# SCH_12-volt-power-EasyEDA.net
KiCad netlist of a schematic drawn in EasyEDA
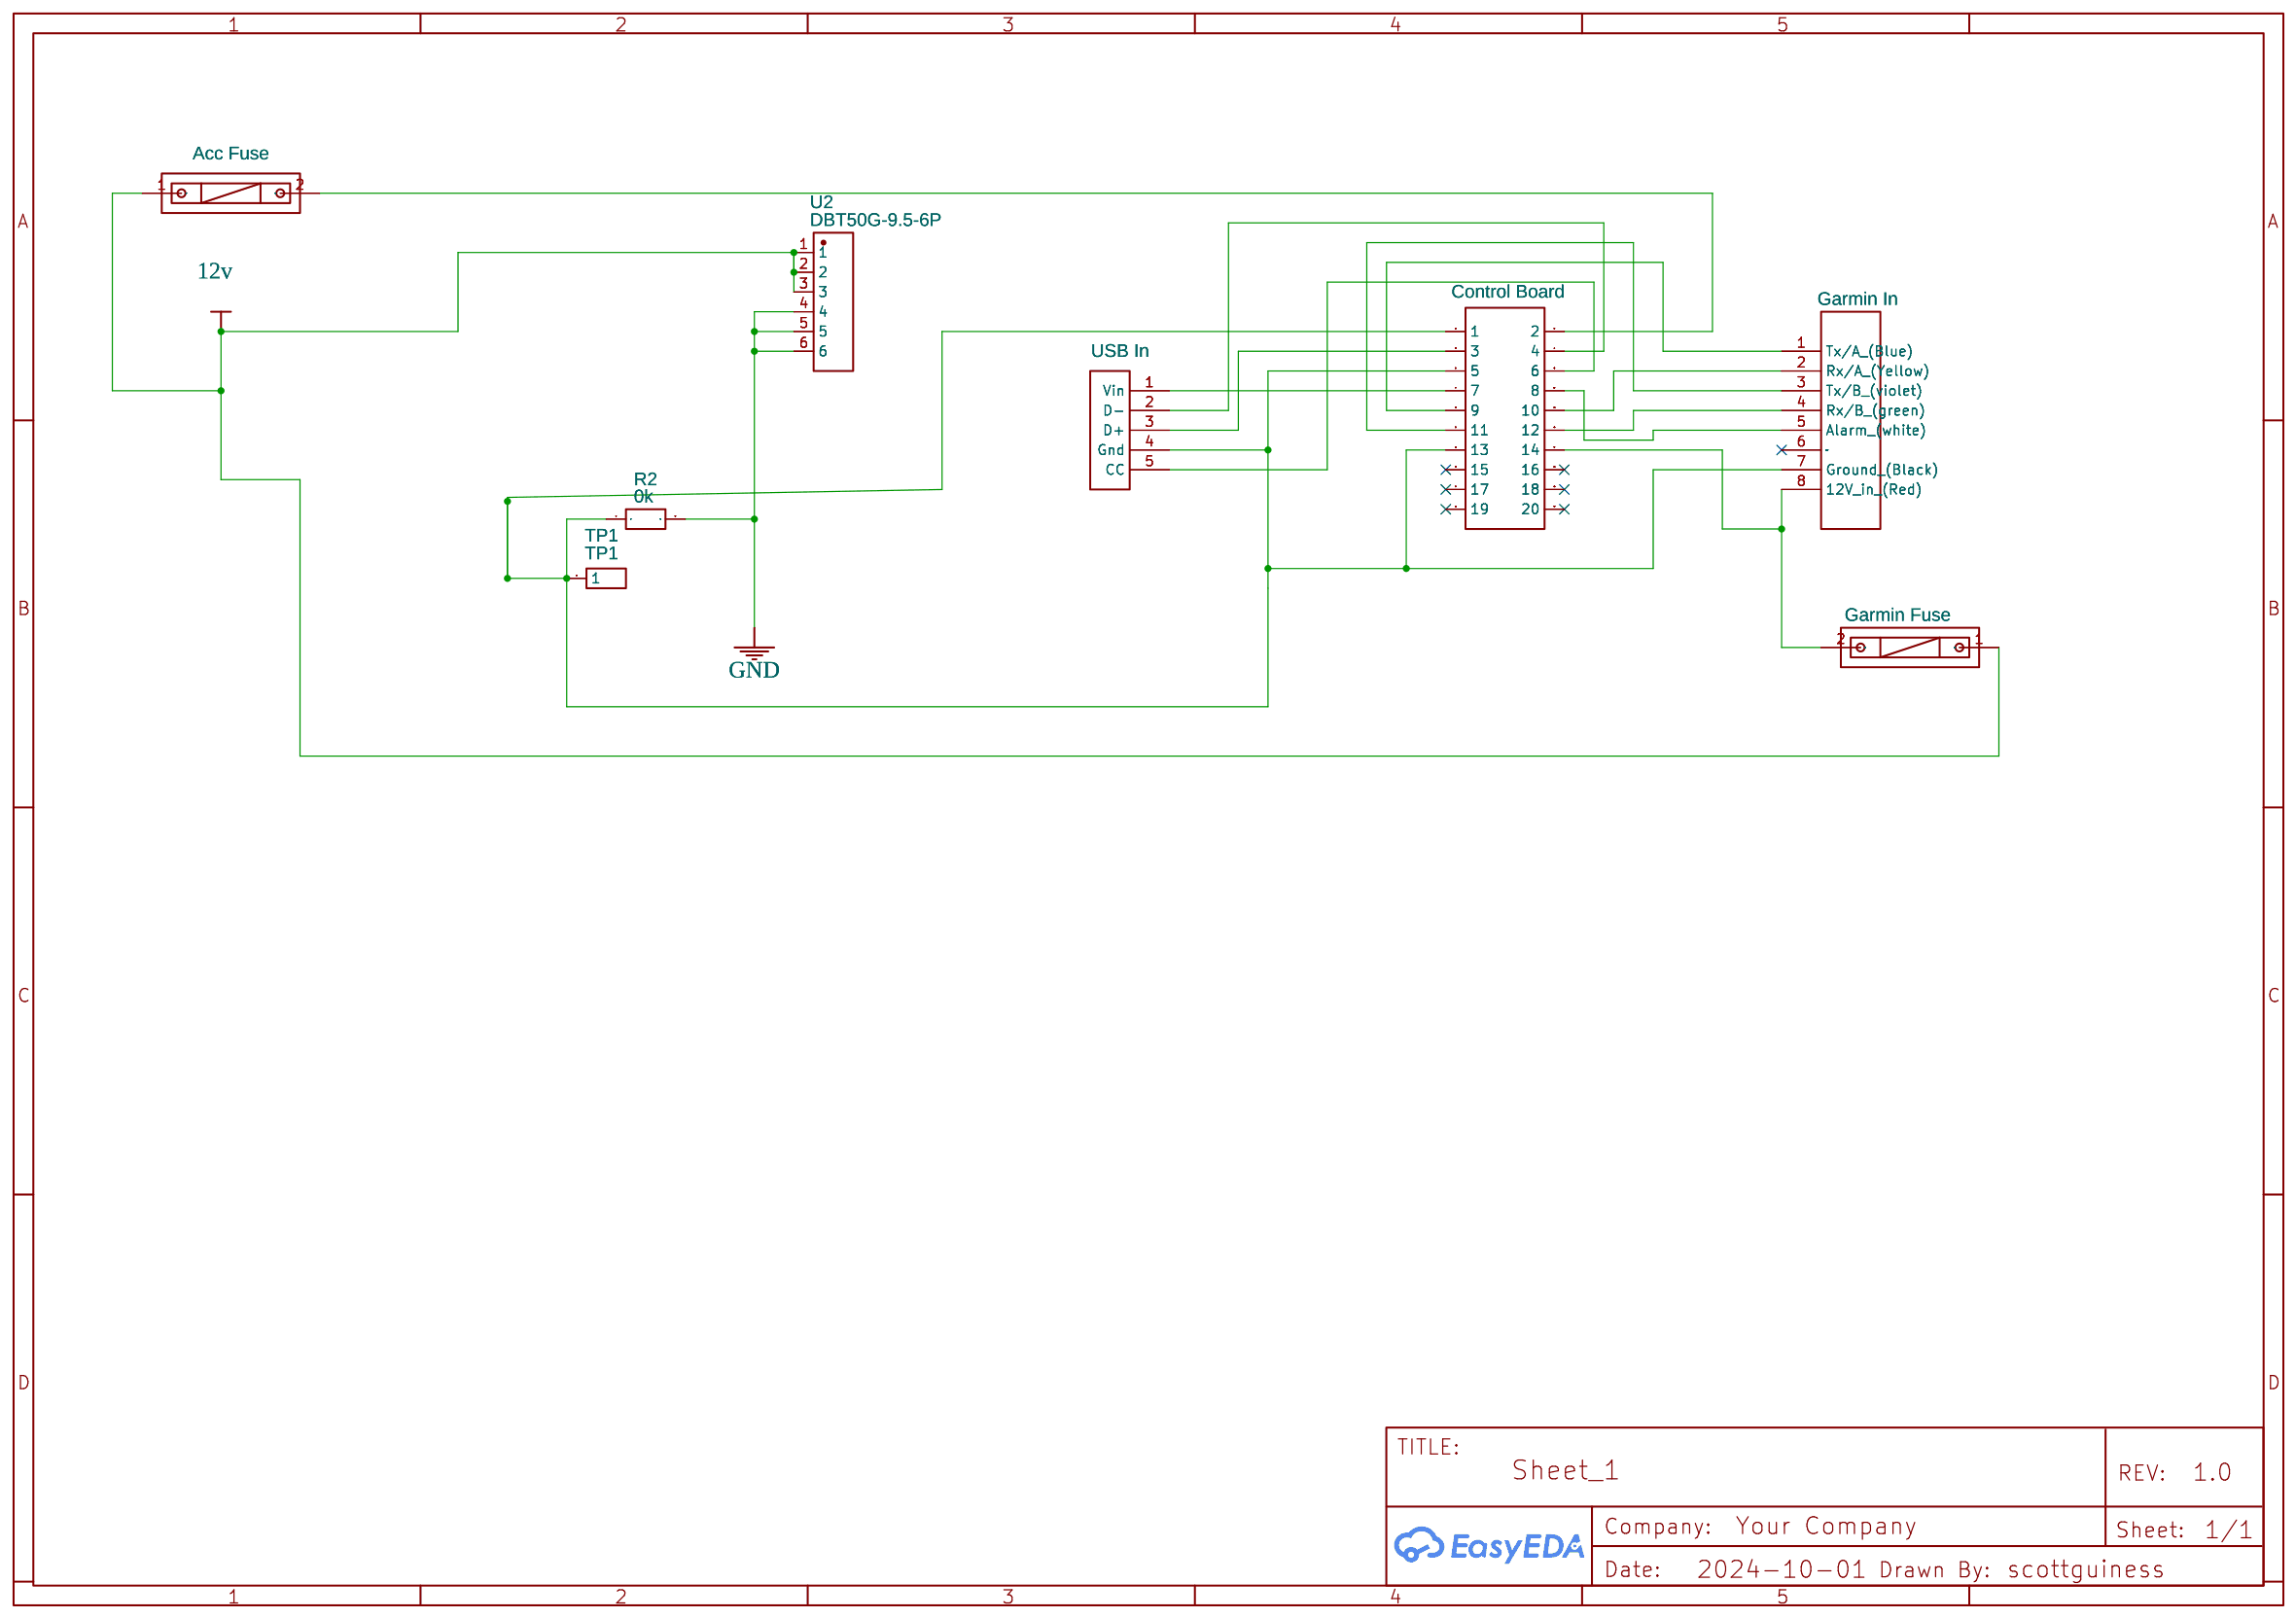
[diagram p0: schematic sheet]

(export (version "E")
  (design (tool "Eeschema 10.0.6"))
  (components
    (comp (ref "ACC-FUSE-5X20=BLX-ATYPE-FUSE-HOLDER")
      (value "Acc Fuse")
      (fields
        (field (name "Manufacturer Part") "5x20 BLX-A型 保险丝支架 XC-7")
        (field (name "Manufacturer") "xcfuse(旭程)")
      )
      (libsource (lib "") (part "5x20 BLX-Atype Fuse holder XC-7_1"))
    )
    (comp (ref "BUTTON_LED1") (value "Control Board") (libsource (lib "") (part "HDR-M-2.54_2x10")))
    (comp (ref "GARMIN-FUSE-5X20-BLX-ATYPE-FUSE-HOLDER")
      (value "Garmin Fuse")
      (fields
        (field (name "Manufacturer Part") "5x20 BLX-A型 保险丝支架 XC-7")
        (field (name "Manufacturer") "xcfuse(旭程)")
      )
      (libsource (lib "") (part "5x20 BLX-Atype Fuse holder XC-7"))
    )
    (comp (ref "GARMIN-GPS")
      (value "Garmin In")
      (fields (field (name "Manufacturer") "Waveshare"))
      (libsource (lib "") (part "8PIN JST CONNECTOR"))
    )
    (comp (ref "R2") (value "0k") (libsource (lib "") (part "R_AXIAL-0.3_EU")))
    (comp (ref "TP1") (value "TP1") (libsource (lib "") (part "HDR-M-2.54_1x1")))
    (comp (ref "U2")
      (value "DBT50G-9.5-6P")
      (fields
        (field (name "Manufacturer Part") "DBT50G-9.5-6P-BK-P OGC")
        (field (name "Manufacturer") "DORABO(地博电气)")
      )
      (libsource (lib "") (part "DBT50G-9.5-6P"))
    )
    (comp (ref "USB-C") (value "USB In") (libsource (lib "") (part "JST XH 1x5")))
  )
  (nets
    (net (code "1") (name "12v") (class "Default")
      (node (ref "ACC-FUSE-5X20=BLX-ATYPE-FUSE-HOLDER") (pin "1") (pinfunction "1_1") (pintype "unspecified"))
      (node (ref "GARMIN-FUSE-5X20-BLX-ATYPE-FUSE-HOLDER") (pin "1") (pinfunction "1_1") (pintype "unspecified"))
      (node (ref "U2") (pin "1") (pinfunction "1_1") (pintype "unspecified"))
      (node (ref "U2") (pin "2") (pinfunction "2_2") (pintype "unspecified"))
      (node (ref "U2") (pin "3") (pinfunction "3_3") (pintype "unspecified"))
    )
    (net (code "2") (name "GND") (class "Default")
      (node (ref "R2") (pin "2") (pinfunction "2_2") (pintype "unspecified"))
      (node (ref "U2") (pin "4") (pinfunction "4_4") (pintype "unspecified"))
      (node (ref "U2") (pin "5") (pinfunction "5_5") (pintype "unspecified"))
      (node (ref "U2") (pin "6") (pinfunction "6_6") (pintype "unspecified"))
    )
    (net (code "3") (name "Net-(ACC-FUSE-5X20=BLX-ATYPE-FUSE-HOLDER-Pad2)") (class "Default")
      (node (ref "ACC-FUSE-5X20=BLX-ATYPE-FUSE-HOLDER") (pin "2") (pinfunction "2_2") (pintype "unspecified"))
      (node (ref "BUTTON_LED1") (pin "2") (pinfunction "2_2") (pintype "unspecified"))
    )
    (net (code "4") (name "Net-(GARMIN-GPS-12V_in_(Red))") (class "Default")
      (node (ref "BUTTON_LED1") (pin "14") (pinfunction "14_14") (pintype "unspecified"))
      (node (ref "GARMIN-FUSE-5X20-BLX-ATYPE-FUSE-HOLDER") (pin "2") (pinfunction "2_2") (pintype "unspecified"))
      (node (ref "GARMIN-GPS") (pin "8") (pinfunction "12V_in_(Red)_8") (pintype "unspecified"))
    )
    (net (code "5") (name "Net-(GARMIN-GPS-Alarm_(white))") (class "Default")
      (node (ref "BUTTON_LED1") (pin "8") (pinfunction "8_8") (pintype "unspecified"))
      (node (ref "GARMIN-GPS") (pin "5") (pinfunction "Alarm_(white)_5") (pintype "unspecified"))
    )
    (net (code "6") (name "Net-(GARMIN-GPS-Ground_(Black))") (class "Default")
      (node (ref "BUTTON_LED1") (pin "1") (pinfunction "1_1") (pintype "unspecified"))
      (node (ref "BUTTON_LED1") (pin "13") (pinfunction "13_13") (pintype "unspecified"))
      (node (ref "BUTTON_LED1") (pin "5") (pinfunction "5_5") (pintype "unspecified"))
      (node (ref "GARMIN-GPS") (pin "7") (pinfunction "Ground_(Black)_7") (pintype "unspecified"))
      (node (ref "R2") (pin "1") (pinfunction "1_1") (pintype "unspecified"))
      (node (ref "TP1") (pin "1") (pinfunction "1_1") (pintype "input"))
      (node (ref "USB-C") (pin "4") (pinfunction "Gnd_4") (pintype "unspecified"))
    )
    (net (code "7") (name "Net-(GARMIN-GPS-Rx{slash}A_(Yellow))") (class "Default")
      (node (ref "BUTTON_LED1") (pin "10") (pinfunction "10_10") (pintype "unspecified"))
      (node (ref "GARMIN-GPS") (pin "2") (pinfunction "Rx/A_(Yellow)_2") (pintype "unspecified"))
    )
    (net (code "8") (name "Net-(GARMIN-GPS-Rx{slash}B_(green))") (class "Default")
      (node (ref "BUTTON_LED1") (pin "12") (pinfunction "12_12") (pintype "unspecified"))
      (node (ref "GARMIN-GPS") (pin "4") (pinfunction "Rx/B_(green)_4") (pintype "unspecified"))
    )
    (net (code "9") (name "Net-(GARMIN-GPS-Tx{slash}A_(Blue))") (class "Default")
      (node (ref "BUTTON_LED1") (pin "9") (pinfunction "9_9") (pintype "unspecified"))
      (node (ref "GARMIN-GPS") (pin "1") (pinfunction "Tx/A_(Blue)_1") (pintype "unspecified"))
    )
    (net (code "10") (name "Net-(GARMIN-GPS-Tx{slash}B_(violet))") (class "Default")
      (node (ref "BUTTON_LED1") (pin "11") (pinfunction "11_11") (pintype "unspecified"))
      (node (ref "GARMIN-GPS") (pin "3") (pinfunction "Tx/B_(violet)_3") (pintype "unspecified"))
    )
    (net (code "11") (name "Net-(USB-C-CC)") (class "Default")
      (node (ref "BUTTON_LED1") (pin "6") (pinfunction "6_6") (pintype "unspecified"))
      (node (ref "USB-C") (pin "5") (pinfunction "CC_5") (pintype "unspecified"))
    )
    (net (code "12") (name "Net-(USB-C-D+)") (class "Default")
      (node (ref "BUTTON_LED1") (pin "3") (pinfunction "3_3") (pintype "unspecified"))
      (node (ref "USB-C") (pin "3") (pinfunction "D+_3") (pintype "unspecified"))
    )
    (net (code "13") (name "Net-(USB-C-D-)") (class "Default")
      (node (ref "BUTTON_LED1") (pin "4") (pinfunction "4_4") (pintype "unspecified"))
      (node (ref "USB-C") (pin "2") (pinfunction "D-_2") (pintype "unspecified"))
    )
    (net (code "14") (name "Net-(USB-C-Vin)") (class "Default")
      (node (ref "BUTTON_LED1") (pin "7") (pinfunction "7_7") (pintype "unspecified"))
      (node (ref "USB-C") (pin "1") (pinfunction "Vin_1") (pintype "unspecified"))
    )
    (net (code "15") (name "unconnected-(BUTTON_LED1-Pad15)") (class "Default")
      (node (ref "BUTTON_LED1") (pin "15") (pinfunction "15_15") (pintype "unspecified+no_connect"))
    )
    (net (code "16") (name "unconnected-(BUTTON_LED1-Pad16)") (class "Default")
      (node (ref "BUTTON_LED1") (pin "16") (pinfunction "16_16") (pintype "unspecified+no_connect"))
    )
    (net (code "17") (name "unconnected-(BUTTON_LED1-Pad17)") (class "Default")
      (node (ref "BUTTON_LED1") (pin "17") (pinfunction "17_17") (pintype "unspecified+no_connect"))
    )
    (net (code "18") (name "unconnected-(BUTTON_LED1-Pad18)") (class "Default")
      (node (ref "BUTTON_LED1") (pin "18") (pinfunction "18_18") (pintype "unspecified+no_connect"))
    )
    (net (code "19") (name "unconnected-(BUTTON_LED1-Pad19)") (class "Default")
      (node (ref "BUTTON_LED1") (pin "19") (pinfunction "19_19") (pintype "unspecified+no_connect"))
    )
    (net (code "20") (name "unconnected-(BUTTON_LED1-Pad20)") (class "Default")
      (node (ref "BUTTON_LED1") (pin "20") (pinfunction "20_20") (pintype "unspecified+no_connect"))
    )
    (net (code "21") (name "unconnected-(GARMIN-GPS-Accessory_On-Pad6)") (class "Default")
      (node (ref "GARMIN-GPS") (pin "6") (pinfunction "Accessory_On_6") (pintype "unspecified+no_connect"))
    )
  )
)
